# DualMotorCape-v7.net
KiCad netlist of a schematic drawn in EAGLE
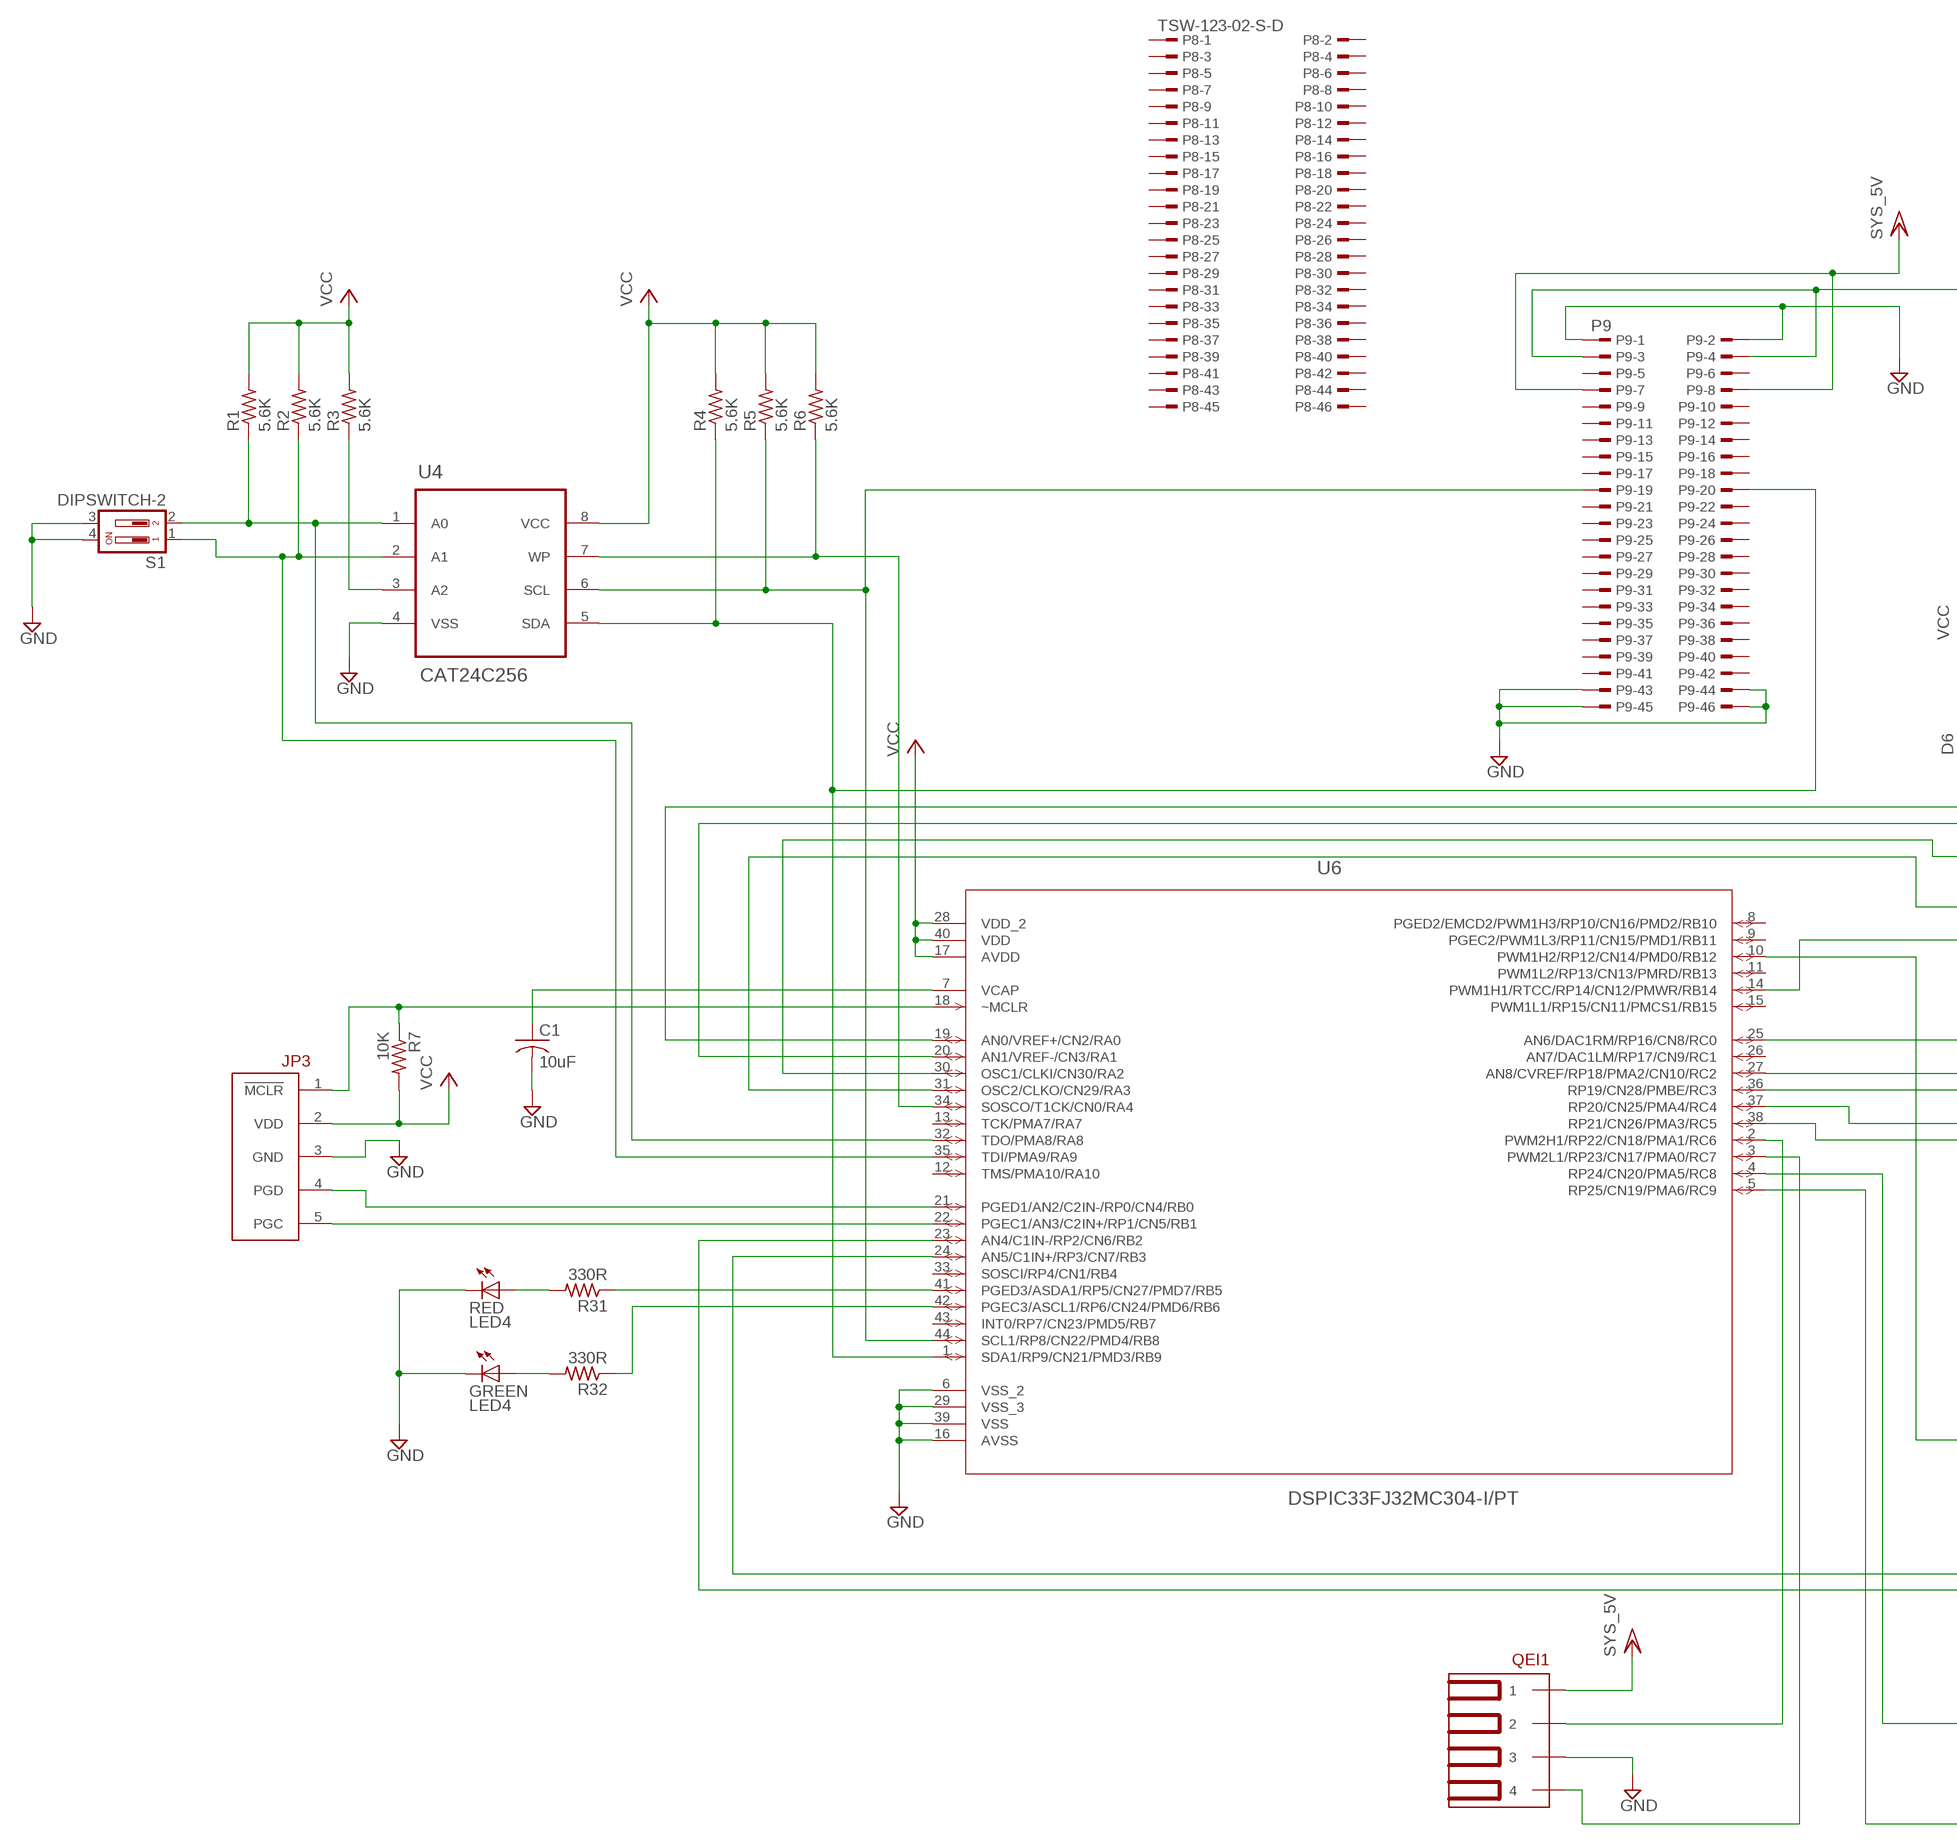
[diagram p0: schematic, sheet 1, part 1 of 2]
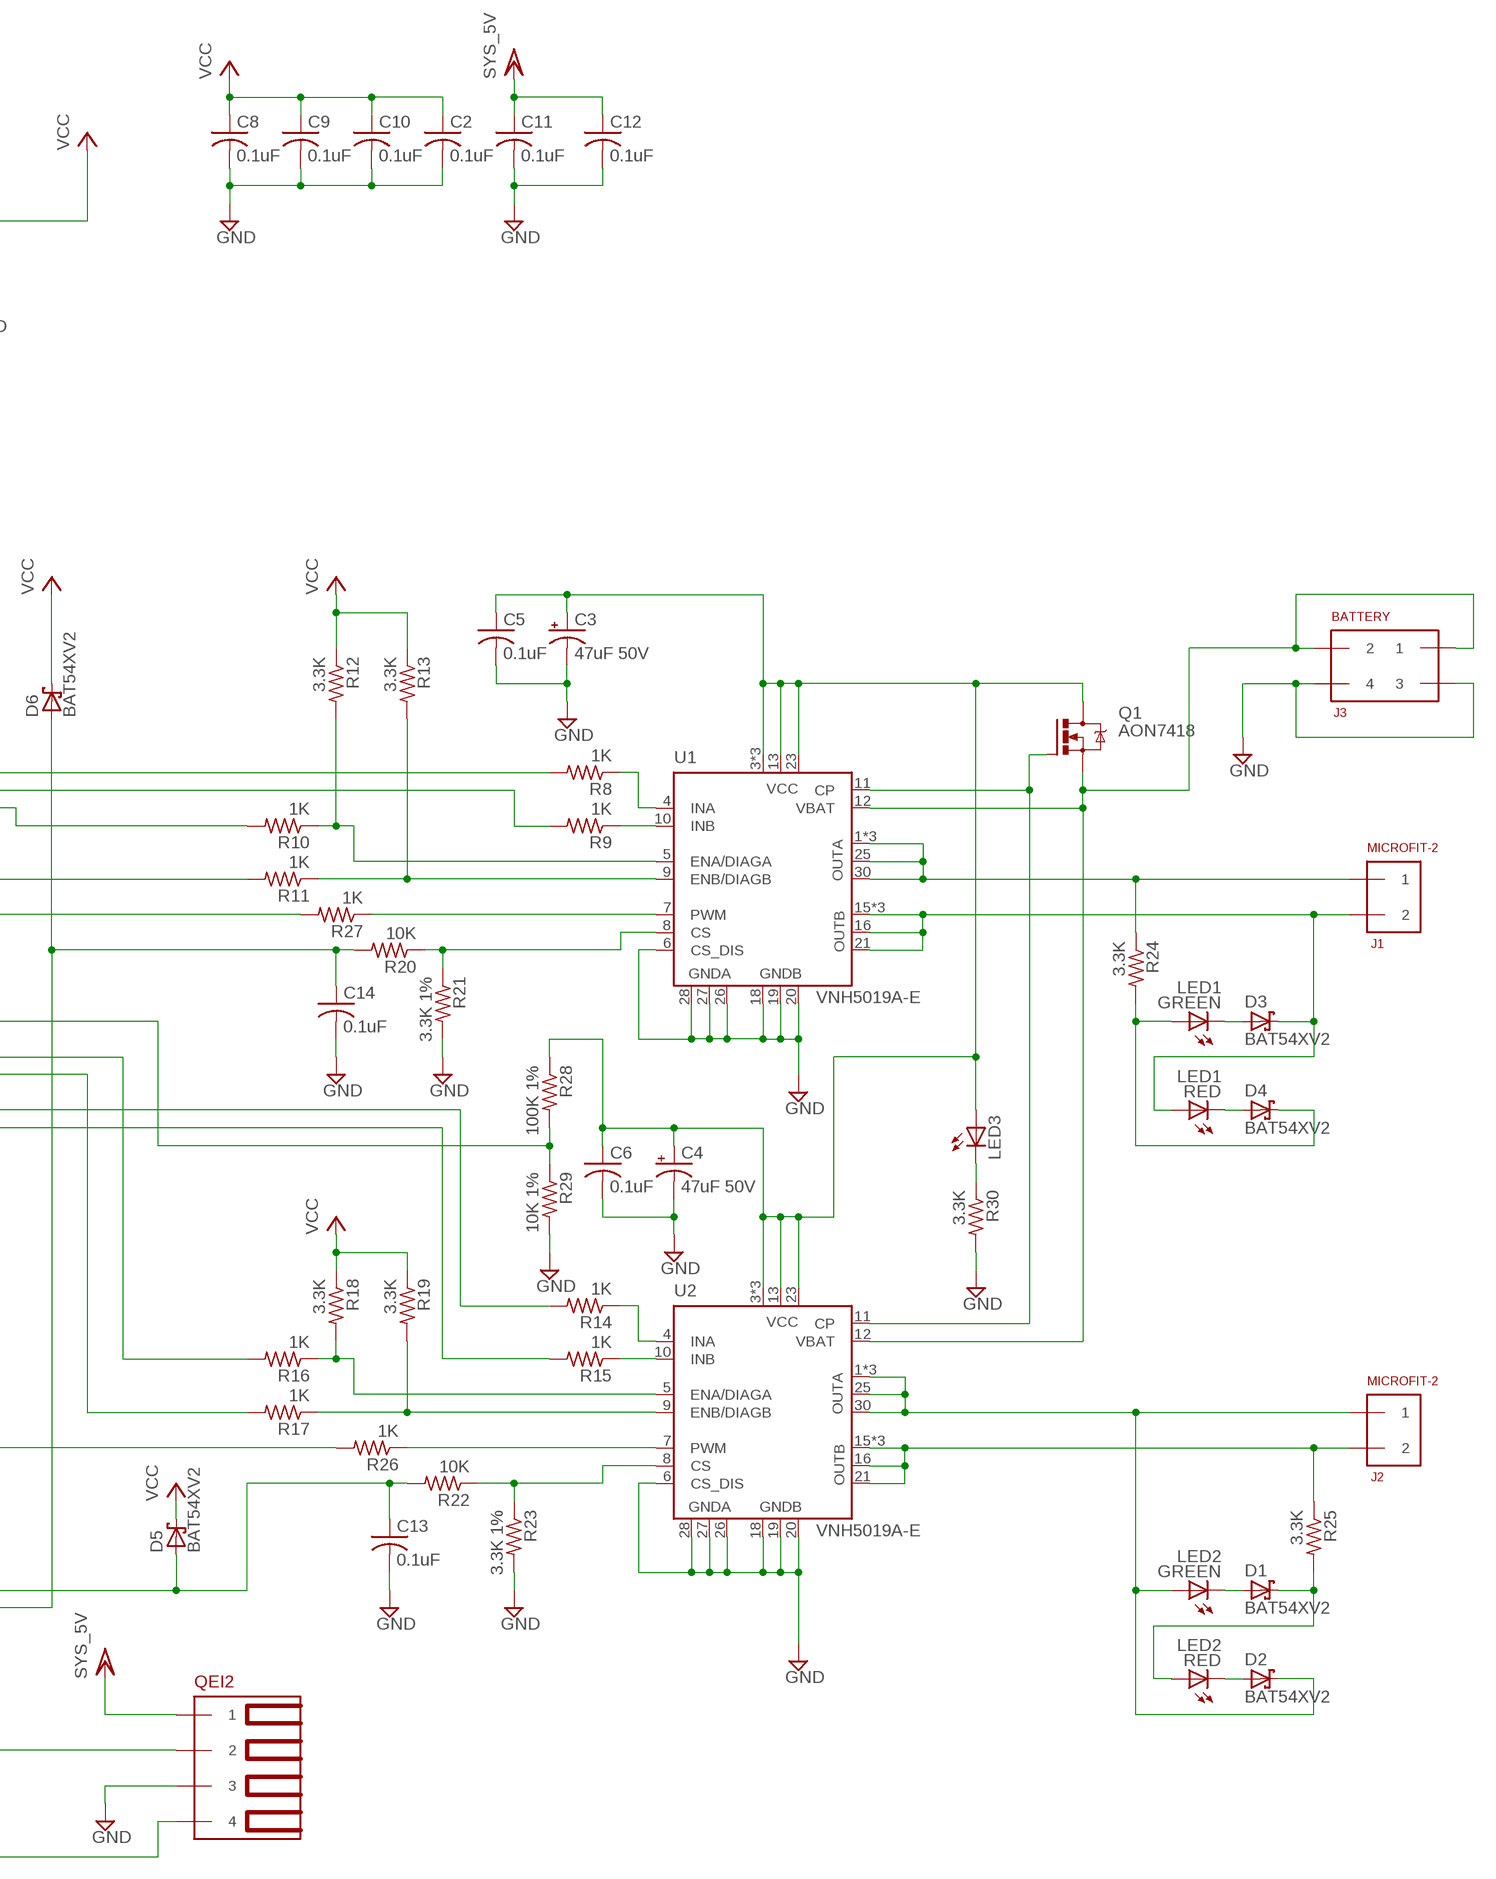
[diagram p1: schematic, sheet 1, part 2 of 2]

(export (version "E")
  (design (tool "Eeschema 10.0.6"))
  (components
    (comp (ref "C1")
      (value "10uF")
      (footprint "eagle-import:C0805")
      (fields (field (name "MPN") "08056C106KAT2A"))
      (libsource (lib "eagle-import") (part "C-USC0805"))
    )
    (comp (ref "C2")
      (value "0.1uF")
      (footprint "eagle-import:C0603")
      (fields (field (name "MPN") "06035C104KAT2A"))
      (libsource (lib "eagle-import") (part "C-USC0603"))
    )
    (comp (ref "C3")
      (value "47uF 50V")
      (footprint "eagle-import:UD-8X10_NICHICON")
      (fields (field (name "MPN") "EEE-FK1H470XP"))
      (libsource (lib "eagle-import") (part "CPOL-USUD-8X10"))
    )
    (comp (ref "C4")
      (value "47uF 50V")
      (footprint "eagle-import:UD-8X10_NICHICON")
      (fields (field (name "MPN") "EEE-FK1H470XP"))
      (libsource (lib "eagle-import") (part "CPOL-USUD-8X10"))
    )
    (comp (ref "C5")
      (value "0.1uF")
      (footprint "eagle-import:C0603")
      (fields (field (name "MPN") "06035C104KAT2A"))
      (libsource (lib "eagle-import") (part "C-USC0603"))
    )
    (comp (ref "C6")
      (value "0.1uF")
      (footprint "eagle-import:C0603")
      (fields (field (name "MPN") "06035C104KAT2A"))
      (libsource (lib "eagle-import") (part "C-USC0603"))
    )
    (comp (ref "C8")
      (value "0.1uF")
      (footprint "eagle-import:C0603")
      (fields (field (name "MPN") "06035C104KAT2A"))
      (libsource (lib "eagle-import") (part "C-USC0603"))
    )
    (comp (ref "C9")
      (value "0.1uF")
      (footprint "eagle-import:C0603")
      (fields (field (name "MPN") "06035C104KAT2A"))
      (libsource (lib "eagle-import") (part "C-USC0603"))
    )
    (comp (ref "C10")
      (value "0.1uF")
      (footprint "eagle-import:C0603")
      (fields (field (name "MPN") "06035C104KAT2A"))
      (libsource (lib "eagle-import") (part "C-USC0603"))
    )
    (comp (ref "C11")
      (value "0.1uF")
      (footprint "eagle-import:C0603")
      (fields (field (name "MPN") "06035C104KAT2A"))
      (libsource (lib "eagle-import") (part "C-USC0603"))
    )
    (comp (ref "C12")
      (value "0.1uF")
      (footprint "eagle-import:C0603")
      (fields (field (name "MPN") "06035C104KAT2A"))
      (libsource (lib "eagle-import") (part "C-USC0603"))
    )
    (comp (ref "C13")
      (value "0.1uF")
      (footprint "eagle-import:C0603")
      (fields (field (name "MPN") "06035C104KAT2A"))
      (libsource (lib "eagle-import") (part "C-USC0603"))
    )
    (comp (ref "C14")
      (value "0.1uF")
      (footprint "eagle-import:C0603")
      (fields (field (name "MPN") "06035C104KAT2A"))
      (libsource (lib "eagle-import") (part "C-USC0603"))
    )
    (comp (ref "D1")
      (value "BAT54XV2")
      (footprint "eagle-import:SOD523")
      (libsource (lib "eagle-import") (part "BAT54XV2"))
    )
    (comp (ref "D2")
      (value "BAT54XV2")
      (footprint "eagle-import:SOD523")
      (libsource (lib "eagle-import") (part "BAT54XV2"))
    )
    (comp (ref "D3")
      (value "BAT54XV2")
      (footprint "eagle-import:SOD523")
      (libsource (lib "eagle-import") (part "BAT54XV2"))
    )
    (comp (ref "D4")
      (value "BAT54XV2")
      (footprint "eagle-import:SOD523")
      (libsource (lib "eagle-import") (part "BAT54XV2"))
    )
    (comp (ref "D5")
      (value "BAT54XV2")
      (footprint "eagle-import:SOD523")
      (libsource (lib "eagle-import") (part "BAT54XV2"))
    )
    (comp (ref "D6")
      (value "BAT54XV2")
      (footprint "eagle-import:SOD523")
      (libsource (lib "eagle-import") (part "BAT54XV2"))
    )
    (comp (ref "J1")
      (value "MICROFIT-2")
      (footprint "eagle-import:MICROFIT-2-R-TH")
      (libsource (lib "eagle-import") (part "MICROFIT-2"))
    )
    (comp (ref "J2")
      (value "MICROFIT-2")
      (footprint "eagle-import:MICROFIT-2-R-TH")
      (libsource (lib "eagle-import") (part "MICROFIT-2"))
    )
    (comp (ref "J3")
      (value "BATTERY")
      (footprint "eagle-import:MICROFIT-4-R-TH")
      (libsource (lib "eagle-import") (part "MICROFIT-4"))
    )
    (comp (ref "JP3")
      (value "ICD2/3-HEADER")
      (footprint "eagle-import:ICD2_3-HEADER")
      (libsource (lib "eagle-import") (part "ICD2/3-HEADER"))
    )
    (comp (ref "LED1")
      (value "KINGBRIGHT-BI-COLOR-LED")
      (footprint "eagle-import:LED-1.6X1.5MM-BI-COLOR")
      (libsource (lib "eagle-import") (part "KINGBRIGHT-BI-COLOR-LED"))
    )
    (comp (ref "LED2")
      (value "KINGBRIGHT-BI-COLOR-LED")
      (footprint "eagle-import:LED-1.6X1.5MM-BI-COLOR")
      (libsource (lib "eagle-import") (part "KINGBRIGHT-BI-COLOR-LED"))
    )
    (comp (ref "LED3")
      (value "LED-LNJP12X8ARA")
      (footprint "eagle-import:LED-603-PANASONIC")
      (libsource (lib "eagle-import") (part "LED-LNJP12X8ARA"))
    )
    (comp (ref "LED4")
      (value "KINGBRIGHT-BI-COLOR-LED")
      (footprint "eagle-import:LED-1.6X1.5MM-BI-COLOR")
      (libsource (lib "eagle-import") (part "KINGBRIGHT-BI-COLOR-LED"))
    )
    (comp (ref "P8")
      (value "TSW-123-02-S-D")
      (footprint "eagle-import:TSW-123-02-S-D")
      (libsource (lib "eagle-import") (part "TSW-123-02-S-D"))
    )
    (comp (ref "P9")
      (value "P9")
      (footprint "eagle-import:TSW-123-02-S-D")
      (libsource (lib "eagle-import") (part "TSW-123-02-S-D"))
    )
    (comp (ref "Q1")
      (value "AON7418")
      (footprint "eagle-import:DFN3.3X3.3")
      (libsource (lib "eagle-import") (part "MOSFET-N"))
    )
    (comp (ref "QEI1")
      (value "MOLEX-KK-22-15-2046-4PIN")
      (footprint "eagle-import:MOLEX-KK-22-15-2046-4PIN")
      (libsource (lib "eagle-import") (part "MOLEX-KK-22-15-2046-4PIN"))
    )
    (comp (ref "QEI2")
      (value "MOLEX-KK-22-15-2046-4PIN")
      (footprint "eagle-import:MOLEX-KK-22-15-2046-4PIN")
      (libsource (lib "eagle-import") (part "MOLEX-KK-22-15-2046-4PIN"))
    )
    (comp (ref "R1")
      (value "5.6K")
      (footprint "eagle-import:R0603")
      (fields (field (name "MF") "FARNELL") (field (name "MPN") "MC 0.063W 0603 1% 5K6"))
      (libsource (lib "eagle-import") (part "R-US_R0603"))
    )
    (comp (ref "R2")
      (value "5.6K")
      (footprint "eagle-import:R0603")
      (fields (field (name "MF") "FARNELL") (field (name "MPN") "MC 0.063W 0603 1% 5K6"))
      (libsource (lib "eagle-import") (part "R-US_R0603"))
    )
    (comp (ref "R3")
      (value "5.6K")
      (footprint "eagle-import:R0603")
      (fields (field (name "MF") "FARNELL") (field (name "MPN") "MC 0.063W 0603 1% 5K6"))
      (libsource (lib "eagle-import") (part "R-US_R0603"))
    )
    (comp (ref "R4")
      (value "5.6K")
      (footprint "eagle-import:R0603")
      (fields (field (name "MF") "FARNELL") (field (name "MPN") "MC 0.063W 0603 1% 5K6"))
      (libsource (lib "eagle-import") (part "R-US_R0603"))
    )
    (comp (ref "R5")
      (value "5.6K")
      (footprint "eagle-import:R0603")
      (fields (field (name "MF") "FARNELL") (field (name "MPN") "MC 0.063W 0603 1% 5K6"))
      (libsource (lib "eagle-import") (part "R-US_R0603"))
    )
    (comp (ref "R6")
      (value "5.6K")
      (footprint "eagle-import:R0603")
      (fields (field (name "MF") "FARNELL") (field (name "MPN") "MC 0.063W 0603 1% 5K6"))
      (libsource (lib "eagle-import") (part "R-US_R0603"))
    )
    (comp (ref "R7")
      (value "10K")
      (footprint "eagle-import:R0603")
      (libsource (lib "eagle-import") (part "R-US_R0603"))
    )
    (comp (ref "R8")
      (value "1K")
      (footprint "eagle-import:R0603")
      (libsource (lib "eagle-import") (part "R-US_R0603"))
    )
    (comp (ref "R9")
      (value "1K")
      (footprint "eagle-import:R0603")
      (libsource (lib "eagle-import") (part "R-US_R0603"))
    )
    (comp (ref "R10")
      (value "1K")
      (footprint "eagle-import:R0603")
      (libsource (lib "eagle-import") (part "R-US_R0603"))
    )
    (comp (ref "R11")
      (value "1K")
      (footprint "eagle-import:R0603")
      (libsource (lib "eagle-import") (part "R-US_R0603"))
    )
    (comp (ref "R12")
      (value "3.3K")
      (footprint "eagle-import:R0603")
      (fields (field (name "MF") "VISHAY/DALE") (field (name "MPN") "CRCW06033K30FKEA"))
      (libsource (lib "eagle-import") (part "R-US_R0603"))
    )
    (comp (ref "R13")
      (value "3.3K")
      (footprint "eagle-import:R0603")
      (fields (field (name "MF") "VISHAY/DALE") (field (name "MPN") "CRCW06033K30FKEA"))
      (libsource (lib "eagle-import") (part "R-US_R0603"))
    )
    (comp (ref "R14")
      (value "1K")
      (footprint "eagle-import:R0603")
      (libsource (lib "eagle-import") (part "R-US_R0603"))
    )
    (comp (ref "R15")
      (value "1K")
      (footprint "eagle-import:R0603")
      (libsource (lib "eagle-import") (part "R-US_R0603"))
    )
    (comp (ref "R16")
      (value "1K")
      (footprint "eagle-import:R0603")
      (libsource (lib "eagle-import") (part "R-US_R0603"))
    )
    (comp (ref "R17")
      (value "1K")
      (footprint "eagle-import:R0603")
      (libsource (lib "eagle-import") (part "R-US_R0603"))
    )
    (comp (ref "R18")
      (value "3.3K")
      (footprint "eagle-import:R0603")
      (fields (field (name "MF") "VISHAY/DALE") (field (name "MPN") "CRCW06033K30FKEA"))
      (libsource (lib "eagle-import") (part "R-US_R0603"))
    )
    (comp (ref "R19")
      (value "3.3K")
      (footprint "eagle-import:R0603")
      (fields (field (name "MF") "VISHAY/DALE") (field (name "MPN") "CRCW06033K30FKEA"))
      (libsource (lib "eagle-import") (part "R-US_R0603"))
    )
    (comp (ref "R20")
      (value "10K")
      (footprint "eagle-import:R0603")
      (libsource (lib "eagle-import") (part "R-US_R0603"))
    )
    (comp (ref "R21")
      (value "3.3K 1%")
      (footprint "eagle-import:R0603")
      (fields (field (name "MF") "VISHAY/DALE") (field (name "MPN") "CRCW06033K30FKEA"))
      (libsource (lib "eagle-import") (part "R-US_R0603"))
    )
    (comp (ref "R22")
      (value "10K")
      (footprint "eagle-import:R0603")
      (libsource (lib "eagle-import") (part "R-US_R0603"))
    )
    (comp (ref "R23")
      (value "3.3K 1%")
      (footprint "eagle-import:R0603")
      (fields (field (name "MF") "VISHAY/DALE") (field (name "MPN") "CRCW06033K30FKEA"))
      (libsource (lib "eagle-import") (part "R-US_R0603"))
    )
    (comp (ref "R24")
      (value "3.3K")
      (footprint "eagle-import:R0603")
      (fields (field (name "MF") "VISHAY/DALE") (field (name "MPN") "CRCW06033K30FKEA"))
      (libsource (lib "eagle-import") (part "R-US_R0603"))
    )
    (comp (ref "R25")
      (value "3.3K")
      (footprint "eagle-import:R0603")
      (fields (field (name "MF") "VISHAY/DALE") (field (name "MPN") "CRCW06033K30FKEA"))
      (libsource (lib "eagle-import") (part "R-US_R0603"))
    )
    (comp (ref "R26")
      (value "1K")
      (footprint "eagle-import:R0603")
      (libsource (lib "eagle-import") (part "R-US_R0603"))
    )
    (comp (ref "R27")
      (value "1K")
      (footprint "eagle-import:R0603")
      (libsource (lib "eagle-import") (part "R-US_R0603"))
    )
    (comp (ref "R28")
      (value "100K 1%")
      (footprint "eagle-import:R0603")
      (fields (field (name "MPN") "ASC0603-100KFT5"))
      (libsource (lib "eagle-import") (part "R-US_R0603"))
    )
    (comp (ref "R29")
      (value "10K 1%")
      (footprint "eagle-import:R0603")
      (fields (field (name "MF") "VISHAY/DALE") (field (name "MPN") "CRCW060310K0FKTA"))
      (libsource (lib "eagle-import") (part "R-US_R0603"))
    )
    (comp (ref "R30")
      (value "3.3K")
      (footprint "eagle-import:R0603")
      (fields (field (name "MF") "VISHAY/DALE") (field (name "MPN") "CRCW06033K30FKEA"))
      (libsource (lib "eagle-import") (part "R-US_R0603"))
    )
    (comp (ref "R31")
      (value "330R")
      (footprint "eagle-import:R0603")
      (libsource (lib "eagle-import") (part "R-US_R0603"))
    )
    (comp (ref "R32")
      (value "330R")
      (footprint "eagle-import:R0603")
      (libsource (lib "eagle-import") (part "R-US_R0603"))
    )
    (comp (ref "S1")
      (value "DIPSWITCH-2")
      (footprint "eagle-import:DIPSWITCH-218-2")
      (libsource (lib "eagle-import") (part "DIPSWITCH-2"))
    )
    (comp (ref "U1")
      (value "VNH5019A-E")
      (footprint "eagle-import:VNH5019A-E")
      (libsource (lib "eagle-import") (part "VNH5019A-E"))
    )
    (comp (ref "U2")
      (value "VNH5019A-E")
      (footprint "eagle-import:VNH5019A-E")
      (libsource (lib "eagle-import") (part "VNH5019A-E"))
    )
    (comp (ref "U4")
      (value "CAT24C256")
      (footprint "eagle-import:SOIC-8")
      (fields (field (name "MPN") "CAT24C256WI-G"))
      (libsource (lib "eagle-import") (part "CAT24C256"))
    )
    (comp (ref "U6")
      (value "DSPIC33FJ32MC304-I/PT")
      (footprint "eagle-import:QFP80P1200X1200X120-44N")
      (fields (field (name "MPN") "dspic33fj32mc304-I/pt") (field (name "MPN_1") "DSPIC33FJ32MC304-I/PT"))
      (libsource (lib "eagle-import") (part "DSPIC33FJ32MC304-I/PT"))
    )
  )
  (nets
    (net (code "1") (name "GND") (class "Default")
      (node (ref "C1") (pin "2") (pinfunction "2_2") (pintype "passive"))
      (node (ref "C10") (pin "2") (pinfunction "2_2") (pintype "passive"))
      (node (ref "C11") (pin "2") (pinfunction "2_2") (pintype "passive"))
      (node (ref "C12") (pin "2") (pinfunction "2_2") (pintype "passive"))
      (node (ref "C13") (pin "2") (pinfunction "2_2") (pintype "passive"))
      (node (ref "C14") (pin "2") (pinfunction "2_2") (pintype "passive"))
      (node (ref "C2") (pin "2") (pinfunction "2_2") (pintype "passive"))
      (node (ref "C3") (pin "-") (pinfunction "-_-") (pintype "passive"))
      (node (ref "C4") (pin "-") (pinfunction "-_-") (pintype "passive"))
      (node (ref "C5") (pin "2") (pinfunction "2_2") (pintype "passive"))
      (node (ref "C6") (pin "2") (pinfunction "2_2") (pintype "passive"))
      (node (ref "C8") (pin "2") (pinfunction "2_2") (pintype "passive"))
      (node (ref "C9") (pin "2") (pinfunction "2_2") (pintype "passive"))
      (node (ref "J3") (pin "3") (pinfunction "4_3") (pintype "passive"))
      (node (ref "J3") (pin "4") (pinfunction "3_4") (pintype "passive"))
      (node (ref "JP3") (pin "3") (pinfunction "GND_3") (pintype "bidirectional"))
      (node (ref "LED4") (pin "2") (pinfunction "2_2") (pintype "passive"))
      (node (ref "LED4") (pin "4") (pinfunction "4_4") (pintype "passive"))
      (node (ref "P9") (pin "1") (pinfunction "1_1") (pintype "passive"))
      (node (ref "P9") (pin "2") (pinfunction "1_2") (pintype "passive"))
      (node (ref "P9") (pin "43") (pinfunction "1_43") (pintype "passive"))
      (node (ref "P9") (pin "44") (pinfunction "1_44") (pintype "passive"))
      (node (ref "P9") (pin "45") (pinfunction "1_45") (pintype "passive"))
      (node (ref "P9") (pin "46") (pinfunction "1_46") (pintype "passive"))
      (node (ref "QEI1") (pin "P$3") (pinfunction "3_P$3") (pintype "passive"))
      (node (ref "QEI2") (pin "P$3") (pinfunction "3_P$3") (pintype "passive"))
      (node (ref "R21") (pin "2") (pinfunction "2_2") (pintype "passive"))
      (node (ref "R23") (pin "2") (pinfunction "2_2") (pintype "passive"))
      (node (ref "R29") (pin "2") (pinfunction "2_2") (pintype "passive"))
      (node (ref "R30") (pin "2") (pinfunction "2_2") (pintype "passive"))
      (node (ref "S1") (pin "3") (pinfunction "3_3") (pintype "passive"))
      (node (ref "S1") (pin "4") (pinfunction "4_4") (pintype "passive"))
      (node (ref "U1") (pin "18") (pinfunction "GNDB_18") (pintype "power_in"))
      (node (ref "U1") (pin "19") (pinfunction "GNDB_19") (pintype "power_in"))
      (node (ref "U1") (pin "20") (pinfunction "GNDB_20") (pintype "power_in"))
      (node (ref "U1") (pin "26") (pinfunction "GNDA_26") (pintype "power_in"))
      (node (ref "U1") (pin "27") (pinfunction "GNDA_27") (pintype "power_in"))
      (node (ref "U1") (pin "28") (pinfunction "GNDA_28") (pintype "power_in"))
      (node (ref "U1") (pin "6") (pinfunction "CS_DIS_6") (pintype "input"))
      (node (ref "U2") (pin "18") (pinfunction "GNDB_18") (pintype "power_in"))
      (node (ref "U2") (pin "19") (pinfunction "GNDB_19") (pintype "power_in"))
      (node (ref "U2") (pin "20") (pinfunction "GNDB_20") (pintype "power_in"))
      (node (ref "U2") (pin "26") (pinfunction "GNDA_26") (pintype "power_in"))
      (node (ref "U2") (pin "27") (pinfunction "GNDA_27") (pintype "power_in"))
      (node (ref "U2") (pin "28") (pinfunction "GNDA_28") (pintype "power_in"))
      (node (ref "U2") (pin "6") (pinfunction "CS_DIS_6") (pintype "input"))
      (node (ref "U4") (pin "4") (pinfunction "VSS_4") (pintype "power_in"))
      (node (ref "U6") (pin "16") (pinfunction "AVSS_16") (pintype "power_in"))
      (node (ref "U6") (pin "29") (pinfunction "VSS_3_29") (pintype "power_in"))
      (node (ref "U6") (pin "39") (pinfunction "VSS_39") (pintype "power_in"))
      (node (ref "U6") (pin "6") (pinfunction "VSS_2_6") (pintype "power_in"))
    )
    (net (code "2") (name "Net-(D1-PadA)") (class "Default")
      (node (ref "D1") (pin "A") (pinfunction "A_A") (pintype "passive"))
      (node (ref "LED2") (pin "4") (pinfunction "4_4") (pintype "passive"))
    )
    (net (code "3") (name "Net-(D1-PadC)") (class "Default")
      (node (ref "D1") (pin "C") (pinfunction "C_C") (pintype "passive"))
      (node (ref "LED2") (pin "1") (pinfunction "1_1") (pintype "passive"))
      (node (ref "R25") (pin "2") (pinfunction "2_2") (pintype "passive"))
    )
    (net (code "4") (name "Net-(D2-PadA)") (class "Default")
      (node (ref "D2") (pin "A") (pinfunction "A_A") (pintype "passive"))
      (node (ref "LED2") (pin "2") (pinfunction "2_2") (pintype "passive"))
    )
    (net (code "5") (name "Net-(D3-PadA)") (class "Default")
      (node (ref "D3") (pin "A") (pinfunction "A_A") (pintype "passive"))
      (node (ref "LED1") (pin "4") (pinfunction "4_4") (pintype "passive"))
    )
    (net (code "6") (name "Net-(D4-PadA)") (class "Default")
      (node (ref "D4") (pin "A") (pinfunction "A_A") (pintype "passive"))
      (node (ref "LED1") (pin "2") (pinfunction "2_2") (pintype "passive"))
    )
    (net (code "7") (name "Net-(D4-PadC)") (class "Default")
      (node (ref "D4") (pin "C") (pinfunction "C_C") (pintype "passive"))
      (node (ref "LED1") (pin "3") (pinfunction "3_3") (pintype "passive"))
      (node (ref "R24") (pin "2") (pinfunction "2_2") (pintype "passive"))
    )
    (net (code "8") (name "Net-(J1-1)") (class "Default")
      (node (ref "J1") (pin "2") (pinfunction "1_2") (pintype "passive"))
      (node (ref "R24") (pin "1") (pinfunction "1_1") (pintype "passive"))
      (node (ref "U1") (pin "1") (pinfunction "OUTA_1") (pintype "output"))
      (node (ref "U1") (pin "25") (pinfunction "OUTA_25") (pintype "passive"))
      (node (ref "U1") (pin "30") (pinfunction "OUTA_30") (pintype "passive"))
      (node (ref "U1") (pin "NC/OUTA") (pinfunction "OUTA_NC/OUTA") (pintype "output"))
      (node (ref "U1") (pin "NC/OUTA@1") (pinfunction "OUTA_NC/OUTA@1") (pintype "output"))
    )
    (net (code "9") (name "Net-(J1-2)") (class "Default")
      (node (ref "D3") (pin "C") (pinfunction "C_C") (pintype "passive"))
      (node (ref "J1") (pin "1") (pinfunction "2_1") (pintype "passive"))
      (node (ref "LED1") (pin "1") (pinfunction "1_1") (pintype "passive"))
      (node (ref "U1") (pin "15") (pinfunction "OUTB_15") (pintype "output"))
      (node (ref "U1") (pin "16") (pinfunction "OUTB_16") (pintype "passive"))
      (node (ref "U1") (pin "21") (pinfunction "OUTB_21") (pintype "passive"))
      (node (ref "U1") (pin "NC/OUTB") (pinfunction "OUTB_NC/OUTB") (pintype "output"))
      (node (ref "U1") (pin "NC/OUTB@1") (pinfunction "OUTB_NC/OUTB@1") (pintype "output"))
    )
    (net (code "10") (name "Net-(J2-1)") (class "Default")
      (node (ref "D2") (pin "C") (pinfunction "C_C") (pintype "passive"))
      (node (ref "J2") (pin "2") (pinfunction "1_2") (pintype "passive"))
      (node (ref "LED2") (pin "3") (pinfunction "3_3") (pintype "passive"))
      (node (ref "U2") (pin "1") (pinfunction "OUTA_1") (pintype "output"))
      (node (ref "U2") (pin "25") (pinfunction "OUTA_25") (pintype "passive"))
      (node (ref "U2") (pin "30") (pinfunction "OUTA_30") (pintype "passive"))
      (node (ref "U2") (pin "NC/OUTA") (pinfunction "OUTA_NC/OUTA") (pintype "output"))
      (node (ref "U2") (pin "NC/OUTA@1") (pinfunction "OUTA_NC/OUTA@1") (pintype "output"))
    )
    (net (code "11") (name "Net-(J2-2)") (class "Default")
      (node (ref "J2") (pin "1") (pinfunction "2_1") (pintype "passive"))
      (node (ref "R25") (pin "1") (pinfunction "1_1") (pintype "passive"))
      (node (ref "U2") (pin "15") (pinfunction "OUTB_15") (pintype "output"))
      (node (ref "U2") (pin "16") (pinfunction "OUTB_16") (pintype "passive"))
      (node (ref "U2") (pin "21") (pinfunction "OUTB_21") (pintype "passive"))
      (node (ref "U2") (pin "NC/OUTB") (pinfunction "OUTB_NC/OUTB") (pintype "output"))
      (node (ref "U2") (pin "NC/OUTB@1") (pinfunction "OUTB_NC/OUTB@1") (pintype "output"))
    )
    (net (code "12") (name "Net-(J3-1)") (class "Default")
      (node (ref "J3") (pin "1") (pinfunction "2_1") (pintype "passive"))
      (node (ref "J3") (pin "2") (pinfunction "1_2") (pintype "passive"))
      (node (ref "Q1") (pin "1") (pinfunction "S_1") (pintype "passive"))
      (node (ref "Q1") (pin "2") (pinfunction "S_2") (pintype "passive"))
      (node (ref "Q1") (pin "3") (pinfunction "S_3") (pintype "passive"))
      (node (ref "U1") (pin "12") (pinfunction "VBAT_12") (pintype "input"))
      (node (ref "U2") (pin "12") (pinfunction "VBAT_12") (pintype "input"))
    )
    (net (code "13") (name "Net-(JP3-PGC)") (class "Default")
      (node (ref "JP3") (pin "5") (pinfunction "PGC_5") (pintype "bidirectional"))
      (node (ref "U6") (pin "22") (pinfunction "PGEC1/AN3/C2IN+/RP1/CN5/RB1_22") (pintype "bidirectional"))
    )
    (net (code "14") (name "Net-(JP3-PGD)") (class "Default")
      (node (ref "JP3") (pin "4") (pinfunction "PGD_4") (pintype "bidirectional"))
      (node (ref "U6") (pin "21") (pinfunction "PGED1/AN2/C2IN-/RP0/CN4/RB0_21") (pintype "bidirectional"))
    )
    (net (code "15") (name "Net-(JP3-~{MCLR})") (class "Default")
      (node (ref "JP3") (pin "1") (pinfunction "~{MCLR}_1") (pintype "bidirectional"))
      (node (ref "R7") (pin "1") (pinfunction "1_1") (pintype "passive"))
      (node (ref "U6") (pin "18") (pinfunction "~{MCLR}_18") (pintype "input"))
    )
    (net (code "16") (name "Net-(LED3-A)") (class "Default")
      (node (ref "C3") (pin "+") (pinfunction "+_+") (pintype "passive"))
      (node (ref "C4") (pin "+") (pinfunction "+_+") (pintype "passive"))
      (node (ref "C5") (pin "1") (pinfunction "1_1") (pintype "passive"))
      (node (ref "C6") (pin "1") (pinfunction "1_1") (pintype "passive"))
      (node (ref "LED3") (pin "1") (pinfunction "A_1") (pintype "passive"))
      (node (ref "Q1") (pin "5") (pinfunction "D_5") (pintype "passive"))
      (node (ref "Q1") (pin "6") (pinfunction "D_6") (pintype "passive"))
      (node (ref "Q1") (pin "7") (pinfunction "D_7") (pintype "passive"))
      (node (ref "Q1") (pin "8") (pinfunction "D_8") (pintype "passive"))
      (node (ref "Q1") (pin "9") (pinfunction "D_9") (pintype "passive"))
      (node (ref "R28") (pin "1") (pinfunction "1_1") (pintype "passive"))
      (node (ref "U1") (pin "13") (pinfunction "VCC_13") (pintype "power_in"))
      (node (ref "U1") (pin "23") (pinfunction "VCC_23") (pintype "power_in"))
      (node (ref "U1") (pin "3") (pinfunction "VCC_3") (pintype "power_in"))
      (node (ref "U1") (pin "NC/VCC") (pinfunction "VCC_NC/VCC") (pintype "power_in"))
      (node (ref "U1") (pin "NC/VCC@1") (pinfunction "VCC_NC/VCC@1") (pintype "power_in"))
      (node (ref "U2") (pin "13") (pinfunction "VCC_13") (pintype "power_in"))
      (node (ref "U2") (pin "23") (pinfunction "VCC_23") (pintype "power_in"))
      (node (ref "U2") (pin "3") (pinfunction "VCC_3") (pintype "power_in"))
      (node (ref "U2") (pin "NC/VCC") (pinfunction "VCC_NC/VCC") (pintype "power_in"))
      (node (ref "U2") (pin "NC/VCC@1") (pinfunction "VCC_NC/VCC@1") (pintype "power_in"))
    )
    (net (code "17") (name "Net-(LED3-C)") (class "Default")
      (node (ref "LED3") (pin "2") (pinfunction "C_2") (pintype "passive"))
      (node (ref "R30") (pin "1") (pinfunction "1_1") (pintype "passive"))
    )
    (net (code "18") (name "Net-(LED4-Pad1)") (class "Default")
      (node (ref "LED4") (pin "1") (pinfunction "1_1") (pintype "passive"))
      (node (ref "R31") (pin "2") (pinfunction "2_2") (pintype "passive"))
    )
    (net (code "19") (name "Net-(LED4-Pad3)") (class "Default")
      (node (ref "LED4") (pin "3") (pinfunction "3_3") (pintype "passive"))
      (node (ref "R32") (pin "2") (pinfunction "2_2") (pintype "passive"))
    )
    (net (code "20") (name "Net-(P9K-1)") (class "Default")
      (node (ref "P9") (pin "19") (pinfunction "1_19") (pintype "passive"))
      (node (ref "R5") (pin "1") (pinfunction "1_1") (pintype "passive"))
      (node (ref "U4") (pin "6") (pinfunction "SCL_6") (pintype "input"))
      (node (ref "U6") (pin "44") (pinfunction "SCL1/RP8/CN22/PMD4/RB8_44") (pintype "bidirectional"))
    )
    (net (code "21") (name "Net-(P9M-1)") (class "Default")
      (node (ref "P9") (pin "20") (pinfunction "1_20") (pintype "passive"))
      (node (ref "R4") (pin "1") (pinfunction "1_1") (pintype "passive"))
      (node (ref "U4") (pin "5") (pinfunction "SDA_5") (pintype "bidirectional"))
      (node (ref "U6") (pin "1") (pinfunction "SDA1/RP9/CN21/PMD3/RB9_1") (pintype "bidirectional"))
    )
    (net (code "22") (name "Net-(Q1-G)") (class "Default")
      (node (ref "Q1") (pin "4") (pinfunction "G_4") (pintype "passive"))
      (node (ref "U1") (pin "11") (pinfunction "CP_11") (pintype "output"))
      (node (ref "U2") (pin "11") (pinfunction "CP_11") (pintype "output"))
    )
    (net (code "23") (name "Net-(QEI1-2)") (class "Default")
      (node (ref "QEI1") (pin "P$2") (pinfunction "2_P$2") (pintype "passive"))
      (node (ref "U6") (pin "2") (pinfunction "PWM2H1/RP22/CN18/PMA1/RC6_2") (pintype "bidirectional"))
    )
    (net (code "24") (name "Net-(QEI1-4)") (class "Default")
      (node (ref "QEI1") (pin "P$4") (pinfunction "4_P$4") (pintype "passive"))
      (node (ref "U6") (pin "3") (pinfunction "PWM2L1/RP23/CN17/PMA0/RC7_3") (pintype "bidirectional"))
    )
    (net (code "25") (name "Net-(QEI2-2)") (class "Default")
      (node (ref "QEI2") (pin "P$2") (pinfunction "2_P$2") (pintype "passive"))
      (node (ref "U6") (pin "4") (pinfunction "RP24/CN20/PMA5/RC8_4") (pintype "bidirectional"))
    )
    (net (code "26") (name "Net-(QEI2-4)") (class "Default")
      (node (ref "QEI2") (pin "P$4") (pinfunction "4_P$4") (pintype "passive"))
      (node (ref "U6") (pin "5") (pinfunction "RP25/CN19/PMA6/RC9_5") (pintype "bidirectional"))
    )
    (net (code "27") (name "Net-(U1-CS)") (class "Default")
      (node (ref "R20") (pin "1") (pinfunction "1_1") (pintype "passive"))
      (node (ref "R21") (pin "1") (pinfunction "1_1") (pintype "passive"))
      (node (ref "U1") (pin "8") (pinfunction "CS_8") (pintype "output"))
    )
    (net (code "28") (name "Net-(U1-ENA{slash}DIAGA)") (class "Default")
      (node (ref "R10") (pin "1") (pinfunction "1_1") (pintype "passive"))
      (node (ref "R12") (pin "2") (pinfunction "2_2") (pintype "passive"))
      (node (ref "U1") (pin "5") (pinfunction "ENA/DIAGA_5") (pintype "open_collector"))
    )
    (net (code "29") (name "Net-(U1-ENB{slash}DIAGB)") (class "Default")
      (node (ref "R11") (pin "1") (pinfunction "1_1") (pintype "passive"))
      (node (ref "R13") (pin "2") (pinfunction "2_2") (pintype "passive"))
      (node (ref "U1") (pin "9") (pinfunction "ENB/DIAGB_9") (pintype "open_collector"))
    )
    (net (code "30") (name "Net-(U1-INA)") (class "Default")
      (node (ref "R8") (pin "1") (pinfunction "1_1") (pintype "passive"))
      (node (ref "U1") (pin "4") (pinfunction "INA_4") (pintype "input"))
    )
    (net (code "31") (name "Net-(U1-INB)") (class "Default")
      (node (ref "R9") (pin "1") (pinfunction "1_1") (pintype "passive"))
      (node (ref "U1") (pin "10") (pinfunction "INB_10") (pintype "input"))
    )
    (net (code "32") (name "Net-(U1-PWM)") (class "Default")
      (node (ref "R27") (pin "1") (pinfunction "1_1") (pintype "passive"))
      (node (ref "U1") (pin "7") (pinfunction "PWM_7") (pintype "input"))
    )
    (net (code "33") (name "Net-(U2-CS)") (class "Default")
      (node (ref "R22") (pin "1") (pinfunction "1_1") (pintype "passive"))
      (node (ref "R23") (pin "1") (pinfunction "1_1") (pintype "passive"))
      (node (ref "U2") (pin "8") (pinfunction "CS_8") (pintype "output"))
    )
    (net (code "34") (name "Net-(U2-ENA{slash}DIAGA)") (class "Default")
      (node (ref "R16") (pin "1") (pinfunction "1_1") (pintype "passive"))
      (node (ref "R18") (pin "2") (pinfunction "2_2") (pintype "passive"))
      (node (ref "U2") (pin "5") (pinfunction "ENA/DIAGA_5") (pintype "open_collector"))
    )
    (net (code "35") (name "Net-(U2-ENB{slash}DIAGB)") (class "Default")
      (node (ref "R17") (pin "1") (pinfunction "1_1") (pintype "passive"))
      (node (ref "R19") (pin "2") (pinfunction "2_2") (pintype "passive"))
      (node (ref "U2") (pin "9") (pinfunction "ENB/DIAGB_9") (pintype "open_collector"))
    )
    (net (code "36") (name "Net-(U2-INA)") (class "Default")
      (node (ref "R14") (pin "1") (pinfunction "1_1") (pintype "passive"))
      (node (ref "U2") (pin "4") (pinfunction "INA_4") (pintype "input"))
    )
    (net (code "37") (name "Net-(U2-INB)") (class "Default")
      (node (ref "R15") (pin "1") (pinfunction "1_1") (pintype "passive"))
      (node (ref "U2") (pin "10") (pinfunction "INB_10") (pintype "input"))
    )
    (net (code "38") (name "Net-(U2-PWM)") (class "Default")
      (node (ref "R26") (pin "1") (pinfunction "1_1") (pintype "passive"))
      (node (ref "U2") (pin "7") (pinfunction "PWM_7") (pintype "input"))
    )
    (net (code "39") (name "Net-(U4-A0)") (class "Default")
      (node (ref "R1") (pin "1") (pinfunction "1_1") (pintype "passive"))
      (node (ref "S1") (pin "2") (pinfunction "2_2") (pintype "passive"))
      (node (ref "U4") (pin "1") (pinfunction "A0_1") (pintype "input"))
      (node (ref "U6") (pin "32") (pinfunction "TDO/PMA8/RA8_32") (pintype "bidirectional"))
    )
    (net (code "40") (name "Net-(U4-A1)") (class "Default")
      (node (ref "R2") (pin "1") (pinfunction "1_1") (pintype "passive"))
      (node (ref "S1") (pin "1") (pinfunction "1_1") (pintype "passive"))
      (node (ref "U4") (pin "2") (pinfunction "A1_2") (pintype "input"))
      (node (ref "U6") (pin "35") (pinfunction "TDI/PMA9/RA9_35") (pintype "bidirectional"))
    )
    (net (code "41") (name "Net-(U4-A2)") (class "Default")
      (node (ref "R3") (pin "1") (pinfunction "1_1") (pintype "passive"))
      (node (ref "U4") (pin "3") (pinfunction "A2_3") (pintype "input"))
    )
    (net (code "42") (name "Net-(U4-WP)") (class "Default")
      (node (ref "R6") (pin "1") (pinfunction "1_1") (pintype "passive"))
      (node (ref "U4") (pin "7") (pinfunction "WP_7") (pintype "input"))
      (node (ref "U6") (pin "34") (pinfunction "SOSCO/T1CK/CN0/RA4_34") (pintype "bidirectional"))
    )
    (net (code "43") (name "Net-(U6-AN0{slash}VREF+{slash}CN2{slash}RA0)") (class "Default")
      (node (ref "R8") (pin "2") (pinfunction "2_2") (pintype "passive"))
      (node (ref "U6") (pin "19") (pinfunction "AN0/VREF+/CN2/RA0_19") (pintype "bidirectional"))
    )
    (net (code "44") (name "Net-(U6-AN1{slash}VREF-{slash}CN3{slash}RA1)") (class "Default")
      (node (ref "R9") (pin "2") (pinfunction "2_2") (pintype "passive"))
      (node (ref "U6") (pin "20") (pinfunction "AN1/VREF-/CN3/RA1_20") (pintype "bidirectional"))
    )
    (net (code "45") (name "Net-(U6-AN4{slash}C1IN-{slash}RP2{slash}CN6{slash}RB2)") (class "Default")
      (node (ref "C14") (pin "1") (pinfunction "1_1") (pintype "passive"))
      (node (ref "D6") (pin "A") (pinfunction "A_A") (pintype "passive"))
      (node (ref "R20") (pin "2") (pinfunction "2_2") (pintype "passive"))
      (node (ref "U6") (pin "23") (pinfunction "AN4/C1IN-/RP2/CN6/RB2_23") (pintype "bidirectional"))
    )
    (net (code "46") (name "Net-(U6-AN5{slash}C1IN+{slash}RP3{slash}CN7{slash}RB3)") (class "Default")
      (node (ref "C13") (pin "1") (pinfunction "1_1") (pintype "passive"))
      (node (ref "D5") (pin "A") (pinfunction "A_A") (pintype "passive"))
      (node (ref "R22") (pin "2") (pinfunction "2_2") (pintype "passive"))
      (node (ref "U6") (pin "24") (pinfunction "AN5/C1IN+/RP3/CN7/RB3_24") (pintype "bidirectional"))
    )
    (net (code "47") (name "Net-(U6-AN6{slash}DAC1RM{slash}RP16{slash}CN8{slash}RC0)") (class "Default")
      (node (ref "R28") (pin "2") (pinfunction "2_2") (pintype "passive"))
      (node (ref "R29") (pin "1") (pinfunction "1_1") (pintype "passive"))
      (node (ref "U6") (pin "25") (pinfunction "AN6/DAC1RM/RP16/CN8/RC0_25") (pintype "bidirectional"))
    )
    (net (code "48") (name "Net-(U6-AN8{slash}CVREF{slash}RP18{slash}PMA2{slash}CN10{slash}RC2)") (class "Default")
      (node (ref "R16") (pin "2") (pinfunction "2_2") (pintype "passive"))
      (node (ref "U6") (pin "27") (pinfunction "AN8/CVREF/RP18/PMA2/CN10/RC2_27") (pintype "bidirectional"))
    )
    (net (code "49") (name "Net-(U6-OSC1{slash}CLKI{slash}CN30{slash}RA2)") (class "Default")
      (node (ref "R10") (pin "2") (pinfunction "2_2") (pintype "passive"))
      (node (ref "U6") (pin "30") (pinfunction "OSC1/CLKI/CN30/RA2_30") (pintype "bidirectional"))
    )
    (net (code "50") (name "Net-(U6-OSC2{slash}CLKO{slash}CN29{slash}RA3)") (class "Default")
      (node (ref "R11") (pin "2") (pinfunction "2_2") (pintype "passive"))
      (node (ref "U6") (pin "31") (pinfunction "OSC2/CLKO/CN29/RA3_31") (pintype "bidirectional"))
    )
    (net (code "51") (name "Net-(U6-PGEC3{slash}ASCL1{slash}RP6{slash}CN24{slash}PMD6{slash}RB6)") (class "Default")
      (node (ref "R32") (pin "1") (pinfunction "1_1") (pintype "passive"))
      (node (ref "U6") (pin "42") (pinfunction "PGEC3/ASCL1/RP6/CN24/PMD6/RB6_42") (pintype "bidirectional"))
    )
    (net (code "52") (name "Net-(U6-PGED3{slash}ASDA1{slash}RP5{slash}CN27{slash}PMD7{slash}RB5)") (class "Default")
      (node (ref "R31") (pin "1") (pinfunction "1_1") (pintype "passive"))
      (node (ref "U6") (pin "41") (pinfunction "PGED3/ASDA1/RP5/CN27/PMD7/RB5_41") (pintype "bidirectional"))
    )
    (net (code "53") (name "Net-(U6-PWM1H1{slash}RTCC{slash}RP14{slash}CN12{slash}PMWR{slash}RB14)") (class "Default")
      (node (ref "R27") (pin "2") (pinfunction "2_2") (pintype "passive"))
      (node (ref "U6") (pin "14") (pinfunction "PWM1H1/RTCC/RP14/CN12/PMWR/RB14_14") (pintype "bidirectional"))
    )
    (net (code "54") (name "Net-(U6-PWM1H2{slash}RP12{slash}CN14{slash}PMD0{slash}RB12)") (class "Default")
      (node (ref "R26") (pin "2") (pinfunction "2_2") (pintype "passive"))
      (node (ref "U6") (pin "10") (pinfunction "PWM1H2/RP12/CN14/PMD0/RB12_10") (pintype "bidirectional"))
    )
    (net (code "55") (name "Net-(U6-RP19{slash}CN28{slash}PMBE{slash}RC3)") (class "Default")
      (node (ref "R17") (pin "2") (pinfunction "2_2") (pintype "passive"))
      (node (ref "U6") (pin "36") (pinfunction "RP19/CN28/PMBE/RC3_36") (pintype "bidirectional"))
    )
    (net (code "56") (name "Net-(U6-RP20{slash}CN25{slash}PMA4{slash}RC4)") (class "Default")
      (node (ref "R14") (pin "2") (pinfunction "2_2") (pintype "passive"))
      (node (ref "U6") (pin "37") (pinfunction "RP20/CN25/PMA4/RC4_37") (pintype "bidirectional"))
    )
    (net (code "57") (name "Net-(U6-RP21{slash}CN26{slash}PMA3{slash}RC5)") (class "Default")
      (node (ref "R15") (pin "2") (pinfunction "2_2") (pintype "passive"))
      (node (ref "U6") (pin "38") (pinfunction "RP21/CN26/PMA3/RC5_38") (pintype "bidirectional"))
    )
    (net (code "58") (name "Net-(U6-VCAP)") (class "Default")
      (node (ref "C1") (pin "1") (pinfunction "1_1") (pintype "passive"))
      (node (ref "U6") (pin "7") (pinfunction "VCAP_7") (pintype "power_in"))
    )
    (net (code "59") (name "SYS_5V") (class "Default")
      (node (ref "C11") (pin "1") (pinfunction "1_1") (pintype "passive"))
      (node (ref "C12") (pin "1") (pinfunction "1_1") (pintype "passive"))
      (node (ref "P9") (pin "7") (pinfunction "1_7") (pintype "passive"))
      (node (ref "P9") (pin "8") (pinfunction "1_8") (pintype "passive"))
      (node (ref "QEI1") (pin "P$1") (pinfunction "1_P$1") (pintype "passive"))
      (node (ref "QEI2") (pin "P$1") (pinfunction "1_P$1") (pintype "passive"))
    )
    (net (code "60") (name "VCC") (class "Default")
      (node (ref "C10") (pin "1") (pinfunction "1_1") (pintype "passive"))
      (node (ref "C2") (pin "1") (pinfunction "1_1") (pintype "passive"))
      (node (ref "C8") (pin "1") (pinfunction "1_1") (pintype "passive"))
      (node (ref "C9") (pin "1") (pinfunction "1_1") (pintype "passive"))
      (node (ref "D5") (pin "C") (pinfunction "C_C") (pintype "passive"))
      (node (ref "D6") (pin "C") (pinfunction "C_C") (pintype "passive"))
      (node (ref "JP3") (pin "2") (pinfunction "VDD_2") (pintype "bidirectional"))
      (node (ref "P9") (pin "3") (pinfunction "1_3") (pintype "passive"))
      (node (ref "P9") (pin "4") (pinfunction "1_4") (pintype "passive"))
      (node (ref "R1") (pin "2") (pinfunction "2_2") (pintype "passive"))
      (node (ref "R12") (pin "1") (pinfunction "1_1") (pintype "passive"))
      (node (ref "R13") (pin "1") (pinfunction "1_1") (pintype "passive"))
      (node (ref "R18") (pin "1") (pinfunction "1_1") (pintype "passive"))
      (node (ref "R19") (pin "1") (pinfunction "1_1") (pintype "passive"))
      (node (ref "R2") (pin "2") (pinfunction "2_2") (pintype "passive"))
      (node (ref "R3") (pin "2") (pinfunction "2_2") (pintype "passive"))
      (node (ref "R4") (pin "2") (pinfunction "2_2") (pintype "passive"))
      (node (ref "R5") (pin "2") (pinfunction "2_2") (pintype "passive"))
      (node (ref "R6") (pin "2") (pinfunction "2_2") (pintype "passive"))
      (node (ref "R7") (pin "2") (pinfunction "2_2") (pintype "passive"))
      (node (ref "U4") (pin "8") (pinfunction "VCC_8") (pintype "power_in"))
      (node (ref "U6") (pin "17") (pinfunction "AVDD_17") (pintype "power_in"))
      (node (ref "U6") (pin "28") (pinfunction "VDD_2_28") (pintype "power_in"))
      (node (ref "U6") (pin "40") (pinfunction "VDD_40") (pintype "power_in"))
    )
    (net (code "61") (name "unconnected-(P8-Pad1)") (class "Default")
      (node (ref "P8") (pin "1") (pinfunction "1_1") (pintype "passive"))
    )
    (net (code "62") (name "unconnected-(P8AA-1-Pad33)") (class "Default")
      (node (ref "P8") (pin "33") (pinfunction "1_33") (pintype "passive"))
    )
    (net (code "63") (name "unconnected-(P8AB-1-Pad34)") (class "Default")
      (node (ref "P8") (pin "34") (pinfunction "1_34") (pintype "passive"))
    )
    (net (code "64") (name "unconnected-(P8AC-1-Pad35)") (class "Default")
      (node (ref "P8") (pin "35") (pinfunction "1_35") (pintype "passive"))
    )
    (net (code "65") (name "unconnected-(P8AD-1-Pad36)") (class "Default")
      (node (ref "P8") (pin "36") (pinfunction "1_36") (pintype "passive"))
    )
    (net (code "66") (name "unconnected-(P8AE-1-Pad37)") (class "Default")
      (node (ref "P8") (pin "37") (pinfunction "1_37") (pintype "passive"))
    )
    (net (code "67") (name "unconnected-(P8AF-1-Pad38)") (class "Default")
      (node (ref "P8") (pin "38") (pinfunction "1_38") (pintype "passive"))
    )
    (net (code "68") (name "unconnected-(P8AG-1-Pad39)") (class "Default")
      (node (ref "P8") (pin "39") (pinfunction "1_39") (pintype "passive"))
    )
    (net (code "69") (name "unconnected-(P8AH-1-Pad4)") (class "Default")
      (node (ref "P8") (pin "4") (pinfunction "1_4") (pintype "passive"))
    )
    (net (code "70") (name "unconnected-(P8AI-1-Pad40)") (class "Default")
      (node (ref "P8") (pin "40") (pinfunction "1_40") (pintype "passive"))
    )
    (net (code "71") (name "unconnected-(P8AJ-1-Pad41)") (class "Default")
      (node (ref "P8") (pin "41") (pinfunction "1_41") (pintype "passive"))
    )
    (net (code "72") (name "unconnected-(P8AK-1-Pad42)") (class "Default")
      (node (ref "P8") (pin "42") (pinfunction "1_42") (pintype "passive"))
    )
    (net (code "73") (name "unconnected-(P8AL-1-Pad43)") (class "Default")
      (node (ref "P8") (pin "43") (pinfunction "1_43") (pintype "passive"))
    )
    (net (code "74") (name "unconnected-(P8AM-1-Pad44)") (class "Default")
      (node (ref "P8") (pin "44") (pinfunction "1_44") (pintype "passive"))
    )
    (net (code "75") (name "unconnected-(P8AN-1-Pad45)") (class "Default")
      (node (ref "P8") (pin "45") (pinfunction "1_45") (pintype "passive"))
    )
    (net (code "76") (name "unconnected-(P8AO-1-Pad46)") (class "Default")
      (node (ref "P8") (pin "46") (pinfunction "1_46") (pintype "passive"))
    )
    (net (code "77") (name "unconnected-(P8AP-1-Pad5)") (class "Default")
      (node (ref "P8") (pin "5") (pinfunction "1_5") (pintype "passive"))
    )
    (net (code "78") (name "unconnected-(P8AQ-1-Pad6)") (class "Default")
      (node (ref "P8") (pin "6") (pinfunction "1_6") (pintype "passive"))
    )
    (net (code "79") (name "unconnected-(P8AR-1-Pad7)") (class "Default")
      (node (ref "P8") (pin "7") (pinfunction "1_7") (pintype "passive"))
    )
    (net (code "80") (name "unconnected-(P8AS-1-Pad8)") (class "Default")
      (node (ref "P8") (pin "8") (pinfunction "1_8") (pintype "passive"))
    )
    (net (code "81") (name "unconnected-(P8AT-1-Pad9)") (class "Default")
      (node (ref "P8") (pin "9") (pinfunction "1_9") (pintype "passive"))
    )
    (net (code "82") (name "unconnected-(P8B-1-Pad10)") (class "Default")
      (node (ref "P8") (pin "10") (pinfunction "1_10") (pintype "passive"))
    )
    (net (code "83") (name "unconnected-(P8C-1-Pad11)") (class "Default")
      (node (ref "P8") (pin "11") (pinfunction "1_11") (pintype "passive"))
    )
    (net (code "84") (name "unconnected-(P8D-1-Pad12)") (class "Default")
      (node (ref "P8") (pin "12") (pinfunction "1_12") (pintype "passive"))
    )
    (net (code "85") (name "unconnected-(P8E-1-Pad13)") (class "Default")
      (node (ref "P8") (pin "13") (pinfunction "1_13") (pintype "passive"))
    )
    (net (code "86") (name "unconnected-(P8F-1-Pad14)") (class "Default")
      (node (ref "P8") (pin "14") (pinfunction "1_14") (pintype "passive"))
    )
    (net (code "87") (name "unconnected-(P8G-1-Pad15)") (class "Default")
      (node (ref "P8") (pin "15") (pinfunction "1_15") (pintype "passive"))
    )
    (net (code "88") (name "unconnected-(P8H-1-Pad16)") (class "Default")
      (node (ref "P8") (pin "16") (pinfunction "1_16") (pintype "passive"))
    )
    (net (code "89") (name "unconnected-(P8I-1-Pad17)") (class "Default")
      (node (ref "P8") (pin "17") (pinfunction "1_17") (pintype "passive"))
    )
    (net (code "90") (name "unconnected-(P8J-1-Pad18)") (class "Default")
      (node (ref "P8") (pin "18") (pinfunction "1_18") (pintype "passive"))
    )
    (net (code "91") (name "unconnected-(P8K-1-Pad19)") (class "Default")
      (node (ref "P8") (pin "19") (pinfunction "1_19") (pintype "passive"))
    )
    (net (code "92") (name "unconnected-(P8L-1-Pad2)") (class "Default")
      (node (ref "P8") (pin "2") (pinfunction "1_2") (pintype "passive"))
    )
    (net (code "93") (name "unconnected-(P8M-1-Pad20)") (class "Default")
      (node (ref "P8") (pin "20") (pinfunction "1_20") (pintype "passive"))
    )
    (net (code "94") (name "unconnected-(P8N-1-Pad21)") (class "Default")
      (node (ref "P8") (pin "21") (pinfunction "1_21") (pintype "passive"))
    )
    (net (code "95") (name "unconnected-(P8O-1-Pad22)") (class "Default")
      (node (ref "P8") (pin "22") (pinfunction "1_22") (pintype "passive"))
    )
    (net (code "96") (name "unconnected-(P8P-1-Pad23)") (class "Default")
      (node (ref "P8") (pin "23") (pinfunction "1_23") (pintype "passive"))
    )
    (net (code "97") (name "unconnected-(P8Q-1-Pad24)") (class "Default")
      (node (ref "P8") (pin "24") (pinfunction "1_24") (pintype "passive"))
    )
    (net (code "98") (name "unconnected-(P8R-1-Pad25)") (class "Default")
      (node (ref "P8") (pin "25") (pinfunction "1_25") (pintype "passive"))
    )
    (net (code "99") (name "unconnected-(P8S-1-Pad26)") (class "Default")
      (node (ref "P8") (pin "26") (pinfunction "1_26") (pintype "passive"))
    )
    (net (code "100") (name "unconnected-(P8T-1-Pad27)") (class "Default")
      (node (ref "P8") (pin "27") (pinfunction "1_27") (pintype "passive"))
    )
    (net (code "101") (name "unconnected-(P8U-1-Pad28)") (class "Default")
      (node (ref "P8") (pin "28") (pinfunction "1_28") (pintype "passive"))
    )
    (net (code "102") (name "unconnected-(P8V-1-Pad29)") (class "Default")
      (node (ref "P8") (pin "29") (pinfunction "1_29") (pintype "passive"))
    )
    (net (code "103") (name "unconnected-(P8W-1-Pad3)") (class "Default")
      (node (ref "P8") (pin "3") (pinfunction "1_3") (pintype "passive"))
    )
    (net (code "104") (name "unconnected-(P8X-1-Pad30)") (class "Default")
      (node (ref "P8") (pin "30") (pinfunction "1_30") (pintype "passive"))
    )
    (net (code "105") (name "unconnected-(P8Y-1-Pad31)") (class "Default")
      (node (ref "P8") (pin "31") (pinfunction "1_31") (pintype "passive"))
    )
    (net (code "106") (name "unconnected-(P8Z-1-Pad32)") (class "Default")
      (node (ref "P8") (pin "32") (pinfunction "1_32") (pintype "passive"))
    )
    (net (code "107") (name "unconnected-(P9AA-1-Pad33)") (class "Default")
      (node (ref "P9") (pin "33") (pinfunction "1_33") (pintype "passive"))
    )
    (net (code "108") (name "unconnected-(P9AB-1-Pad34)") (class "Default")
      (node (ref "P9") (pin "34") (pinfunction "1_34") (pintype "passive"))
    )
    (net (code "109") (name "unconnected-(P9AC-1-Pad35)") (class "Default")
      (node (ref "P9") (pin "35") (pinfunction "1_35") (pintype "passive"))
    )
    (net (code "110") (name "unconnected-(P9AD-1-Pad36)") (class "Default")
      (node (ref "P9") (pin "36") (pinfunction "1_36") (pintype "passive"))
    )
    (net (code "111") (name "unconnected-(P9AE-1-Pad37)") (class "Default")
      (node (ref "P9") (pin "37") (pinfunction "1_37") (pintype "passive"))
    )
    (net (code "112") (name "unconnected-(P9AF-1-Pad38)") (class "Default")
      (node (ref "P9") (pin "38") (pinfunction "1_38") (pintype "passive"))
    )
    (net (code "113") (name "unconnected-(P9AG-1-Pad39)") (class "Default")
      (node (ref "P9") (pin "39") (pinfunction "1_39") (pintype "passive"))
    )
    (net (code "114") (name "unconnected-(P9AI-1-Pad40)") (class "Default")
      (node (ref "P9") (pin "40") (pinfunction "1_40") (pintype "passive"))
    )
    (net (code "115") (name "unconnected-(P9AJ-1-Pad41)") (class "Default")
      (node (ref "P9") (pin "41") (pinfunction "1_41") (pintype "passive"))
    )
    (net (code "116") (name "unconnected-(P9AK-1-Pad42)") (class "Default")
      (node (ref "P9") (pin "42") (pinfunction "1_42") (pintype "passive"))
    )
    (net (code "117") (name "unconnected-(P9AP-1-Pad5)") (class "Default")
      (node (ref "P9") (pin "5") (pinfunction "1_5") (pintype "passive"))
    )
    (net (code "118") (name "unconnected-(P9AQ-1-Pad6)") (class "Default")
      (node (ref "P9") (pin "6") (pinfunction "1_6") (pintype "passive"))
    )
    (net (code "119") (name "unconnected-(P9AT-1-Pad9)") (class "Default")
      (node (ref "P9") (pin "9") (pinfunction "1_9") (pintype "passive"))
    )
    (net (code "120") (name "unconnected-(P9B-1-Pad10)") (class "Default")
      (node (ref "P9") (pin "10") (pinfunction "1_10") (pintype "passive"))
    )
    (net (code "121") (name "unconnected-(P9C-1-Pad11)") (class "Default")
      (node (ref "P9") (pin "11") (pinfunction "1_11") (pintype "passive"))
    )
    (net (code "122") (name "unconnected-(P9D-1-Pad12)") (class "Default")
      (node (ref "P9") (pin "12") (pinfunction "1_12") (pintype "passive"))
    )
    (net (code "123") (name "unconnected-(P9E-1-Pad13)") (class "Default")
      (node (ref "P9") (pin "13") (pinfunction "1_13") (pintype "passive"))
    )
    (net (code "124") (name "unconnected-(P9F-1-Pad14)") (class "Default")
      (node (ref "P9") (pin "14") (pinfunction "1_14") (pintype "passive"))
    )
    (net (code "125") (name "unconnected-(P9G-1-Pad15)") (class "Default")
      (node (ref "P9") (pin "15") (pinfunction "1_15") (pintype "passive"))
    )
    (net (code "126") (name "unconnected-(P9H-1-Pad16)") (class "Default")
      (node (ref "P9") (pin "16") (pinfunction "1_16") (pintype "passive"))
    )
    (net (code "127") (name "unconnected-(P9I-1-Pad17)") (class "Default")
      (node (ref "P9") (pin "17") (pinfunction "1_17") (pintype "passive"))
    )
    (net (code "128") (name "unconnected-(P9J-1-Pad18)") (class "Default")
      (node (ref "P9") (pin "18") (pinfunction "1_18") (pintype "passive"))
    )
    (net (code "129") (name "unconnected-(P9N-1-Pad21)") (class "Default")
      (node (ref "P9") (pin "21") (pinfunction "1_21") (pintype "passive"))
    )
    (net (code "130") (name "unconnected-(P9O-1-Pad22)") (class "Default")
      (node (ref "P9") (pin "22") (pinfunction "1_22") (pintype "passive"))
    )
    (net (code "131") (name "unconnected-(P9P-1-Pad23)") (class "Default")
      (node (ref "P9") (pin "23") (pinfunction "1_23") (pintype "passive"))
    )
    (net (code "132") (name "unconnected-(P9Q-1-Pad24)") (class "Default")
      (node (ref "P9") (pin "24") (pinfunction "1_24") (pintype "passive"))
    )
    (net (code "133") (name "unconnected-(P9R-1-Pad25)") (class "Default")
      (node (ref "P9") (pin "25") (pinfunction "1_25") (pintype "passive"))
    )
    (net (code "134") (name "unconnected-(P9S-1-Pad26)") (class "Default")
      (node (ref "P9") (pin "26") (pinfunction "1_26") (pintype "passive"))
    )
    (net (code "135") (name "unconnected-(P9T-1-Pad27)") (class "Default")
      (node (ref "P9") (pin "27") (pinfunction "1_27") (pintype "passive"))
    )
    (net (code "136") (name "unconnected-(P9U-1-Pad28)") (class "Default")
      (node (ref "P9") (pin "28") (pinfunction "1_28") (pintype "passive"))
    )
    (net (code "137") (name "unconnected-(P9V-1-Pad29)") (class "Default")
      (node (ref "P9") (pin "29") (pinfunction "1_29") (pintype "passive"))
    )
    (net (code "138") (name "unconnected-(P9X-1-Pad30)") (class "Default")
      (node (ref "P9") (pin "30") (pinfunction "1_30") (pintype "passive"))
    )
    (net (code "139") (name "unconnected-(P9Y-1-Pad31)") (class "Default")
      (node (ref "P9") (pin "31") (pinfunction "1_31") (pintype "passive"))
    )
    (net (code "140") (name "unconnected-(P9Z-1-Pad32)") (class "Default")
      (node (ref "P9") (pin "32") (pinfunction "1_32") (pintype "passive"))
    )
    (net (code "141") (name "unconnected-(U6-AN7{slash}DAC1LM{slash}RP17{slash}CN9{slash}RC1-Pad26)") (class "Default")
      (node (ref "U6") (pin "26") (pinfunction "AN7/DAC1LM/RP17/CN9/RC1_26") (pintype "bidirectional"))
    )
    (net (code "142") (name "unconnected-(U6-INT0{slash}RP7{slash}CN23{slash}PMD5{slash}RB7-Pad43)") (class "Default")
      (node (ref "U6") (pin "43") (pinfunction "INT0/RP7/CN23/PMD5/RB7_43") (pintype "bidirectional"))
    )
    (net (code "143") (name "unconnected-(U6-PGEC2{slash}PWM1L3{slash}RP11{slash}CN15{slash}PMD1{slash}RB11-Pad9)") (class "Default")
      (node (ref "U6") (pin "9") (pinfunction "PGEC2/PWM1L3/RP11/CN15/PMD1/RB11_9") (pintype "bidirectional"))
    )
    (net (code "144") (name "unconnected-(U6-PGED2{slash}EMCD2{slash}PWM1H3{slash}RP10{slash}CN16{slash}PMD2{slash}RB10-Pad8)") (class "Default")
      (node (ref "U6") (pin "8") (pinfunction "PGED2/EMCD2/PWM1H3/RP10/CN16/PMD2/RB10_8") (pintype "bidirectional"))
    )
    (net (code "145") (name "unconnected-(U6-PWM1L1{slash}RP15{slash}CN11{slash}PMCS1{slash}RB15-Pad15)") (class "Default")
      (node (ref "U6") (pin "15") (pinfunction "PWM1L1/RP15/CN11/PMCS1/RB15_15") (pintype "bidirectional"))
    )
    (net (code "146") (name "unconnected-(U6-PWM1L2{slash}RP13{slash}CN13{slash}PMRD{slash}RB13-Pad11)") (class "Default")
      (node (ref "U6") (pin "11") (pinfunction "PWM1L2/RP13/CN13/PMRD/RB13_11") (pintype "bidirectional"))
    )
    (net (code "147") (name "unconnected-(U6-SOSCI{slash}RP4{slash}CN1{slash}RB4-Pad33)") (class "Default")
      (node (ref "U6") (pin "33") (pinfunction "SOSCI/RP4/CN1/RB4_33") (pintype "bidirectional"))
    )
    (net (code "148") (name "unconnected-(U6-TCK{slash}PMA7{slash}RA7-Pad13)") (class "Default")
      (node (ref "U6") (pin "13") (pinfunction "TCK/PMA7/RA7_13") (pintype "bidirectional"))
    )
    (net (code "149") (name "unconnected-(U6-TMS{slash}PMA10{slash}RA10-Pad12)") (class "Default")
      (node (ref "U6") (pin "12") (pinfunction "TMS/PMA10/RA10_12") (pintype "bidirectional"))
    )
  )
)
